# 03_MCU.net
KiCad netlist of a schematic drawn in Altium Designer
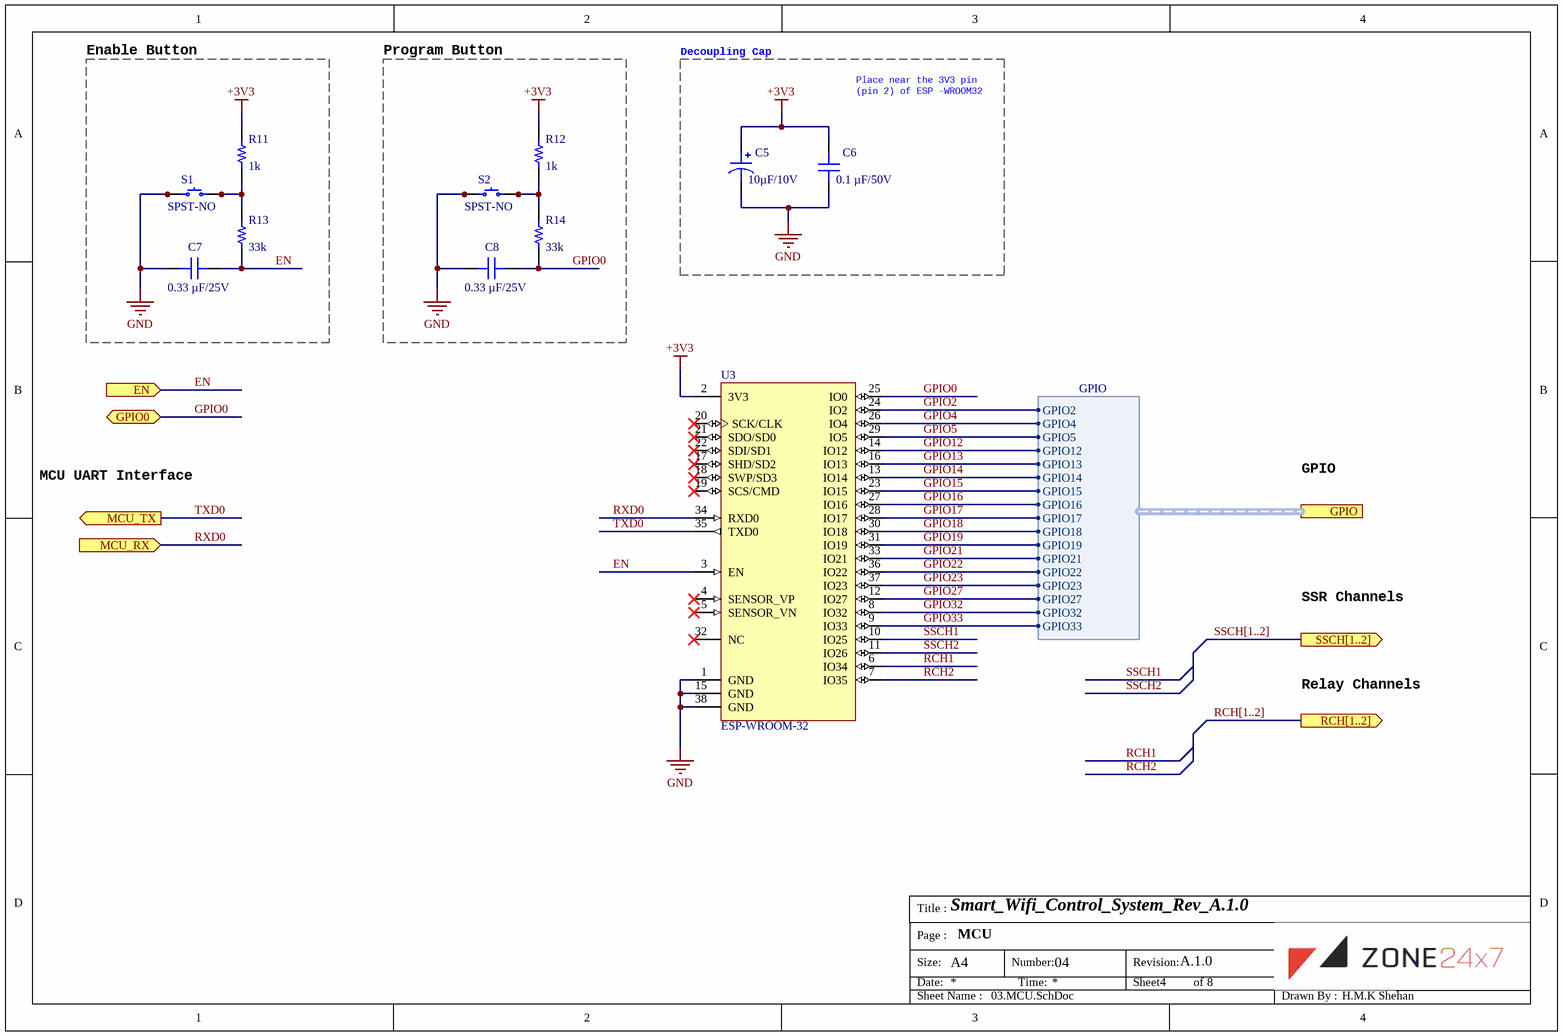
[diagram p0: 03.MCU.SchDoc]

(export (version "E")
  (design (tool "Eeschema 10.0.6"))
  (components
    (comp (ref "C5")
      (value "10µF/10V")
      (footprint "CAP POL 1411_3528")
      (description "10uF 10V 2.1Ω@100kHz ±10% 1411 Tantalum Capacitors ROHS")
      (fields
        (field (name "MANUFACTURER PART NUMBER") "TAJB106K010TNJ")
        (field (name "MANUFACTURER") "AVX Corporation")
      )
      (libsource (lib "Celestial Altium Library - altium_library") (part "Polarised Capacitor"))
    )
    (comp (ref "C6")
      (value "0.1 µF/50V")
      (footprint "CAP 0805_2012")
      (description "50V 100nF 2X1 ±10% 0805 Multilayer Ceramic Capacitors MLCC - SMD/SMT ROHS")
      (fields
        (field (name "MANUFACTURER PART NUMBER") "CT41G-0805-2X1-50V-0.1μF-K(N)")
        (field (name "MANUFACTURER") "TORCH")
      )
      (libsource (lib "Celestial Altium Library - altium_library") (part "Capacitor"))
    )
    (comp (ref "C7")
      (value "0.33 µF/25V")
      (footprint "CAP 0603_1608")
      (description "25V 330nF X7R ±10% 0603 Multilayer Ceramic Capacitors MLCC - SMD/SMT ROHS")
      (fields
        (field (name "MANUFACTURER PART NUMBER") "CC0603KRX7R8BB334")
        (field (name "MANUFACTURER") "Yageo")
      )
      (libsource (lib "Celestial Altium Library - altium_library") (part "Capacitor"))
    )
    (comp (ref "C8")
      (value "0.33 µF/25V")
      (footprint "CAP 0603_1608")
      (description "25V 330nF X7R ±10% 0603 Multilayer Ceramic Capacitors MLCC - SMD/SMT ROHS")
      (fields
        (field (name "MANUFACTURER PART NUMBER") "CC0603KRX7R8BB334")
        (field (name "MANUFACTURER") "Yageo")
      )
      (libsource (lib "Celestial Altium Library - altium_library") (part "Capacitor"))
    )
    (comp (ref "R11")
      (value "1k")
      (footprint "RES 0603_1608")
      (description "100mW ±100ppm/℃ ±1% 1kΩ 0603 Chip Resistor - Surface Mount ROHS")
      (fields (field (name "MANUFACTURER PART NUMBER") "RTT031001FTP") (field (name "MANUFACTURER") "RALEC"))
      (libsource (lib "Celestial Altium Library - altium_library") (part "Resistor"))
    )
    (comp (ref "R12")
      (value "1k")
      (footprint "RES 0603_1608")
      (description "100mW ±100ppm/℃ ±1% 1kΩ 0603 Chip Resistor - Surface Mount ROHS")
      (fields (field (name "MANUFACTURER PART NUMBER") "RTT031001FTP") (field (name "MANUFACTURER") "RALEC"))
      (libsource (lib "Celestial Altium Library - altium_library") (part "Resistor"))
    )
    (comp (ref "R13")
      (value "33k")
      (footprint "RES 0603_1608")
      (description "100mW ±100ppm/℃ ±1% 33kΩ 0603 Chip Resistor - Surface Mount ROHS")
      (fields (field (name "MANUFACTURER PART NUMBER") "RTT033302FTP") (field (name "MANUFACTURER") "RALEC"))
      (libsource (lib "Celestial Altium Library - altium_library") (part "Resistor"))
    )
    (comp (ref "R14")
      (value "33k")
      (footprint "RES 0603_1608")
      (description "100mW ±100ppm/℃ ±1% 33kΩ 0603 Chip Resistor - Surface Mount ROHS")
      (fields (field (name "MANUFACTURER PART NUMBER") "RTT033302FTP") (field (name "MANUFACTURER") "RALEC"))
      (libsource (lib "Celestial Altium Library - altium_library") (part "Resistor"))
    )
    (comp (ref "S1")
      (value "SPST-NO")
      (footprint "TE FSM4JSMA")
      (description "SWITCH TACTILE SPST-NO 0.05A 24V")
      (fields
        (field (name "MANUFACTURER PART NUMBER") "FSM4JSMATR")
        (field (name "MANUFACTURER") "TE Connectivity ALCOSWITCH Switches")
      )
      (libsource (lib "Celestial Altium Library - altium_library") (part "SPST-NO 4 PIN"))
    )
    (comp (ref "S2")
      (value "SPST-NO")
      (footprint "TE FSM4JSMA")
      (description "SWITCH TACTILE SPST-NO 0.05A 24V")
      (fields
        (field (name "MANUFACTURER PART NUMBER") "FSM4JSMATR")
        (field (name "MANUFACTURER") "TE Connectivity ALCOSWITCH Switches")
      )
      (libsource (lib "Celestial Altium Library - altium_library") (part "SPST-NO 4 PIN"))
    )
    (comp (ref "U3")
      (value "ESP-WROOM-32")
      (footprint "OLMX-ESP-WROOM-32")
      (description "SMD,18x25.5mm WiFi Modules ROHS")
      (fields
        (field (name "MANUFACTURER") "Espressif Systems")
        (field (name "MANUFACTURER PART NUMBER") "ESP32-WROOM-32-N4")
      )
      (libsource (lib "Smart_Wifi_Control_System_Rev_A.1.0") (part "OLMX-ESP-WROOM-32-38"))
    )
  )
  (nets
    (net (code "2") (name "+3V3") (class "Default")
      (node (ref "C5") (pin "1") (pinfunction "1_1") (pintype "passive"))
      (node (ref "C6") (pin "2") (pinfunction "2_2") (pintype "passive"))
      (node (ref "R11") (pin "2") (pinfunction "2_2") (pintype "passive"))
      (node (ref "R12") (pin "2") (pinfunction "2_2") (pintype "passive"))
      (node (ref "U3") (pin "2") (pinfunction "3V3_2") (pintype "power_in"))
    )
    (net (code "3") (name "/EN") (class "Default")
      (node (ref "C7") (pin "1") (pinfunction "1_1") (pintype "passive"))
      (node (ref "R13") (pin "1") (pinfunction "1_1") (pintype "passive"))
      (node (ref "U3") (pin "3") (pinfunction "EN_3") (pintype "input"))
    )
    (net (code "4") (name "/GPIO0") (class "Default")
      (node (ref "C8") (pin "1") (pinfunction "1_1") (pintype "passive"))
      (node (ref "R14") (pin "1") (pinfunction "1_1") (pintype "passive"))
      (node (ref "U3") (pin "25") (pinfunction "IO0_25") (pintype "bidirectional"))
    )
    (net (code "5") (name "/GPIO2") (class "Default")
      (node (ref "U3") (pin "24") (pinfunction "IO2_24") (pintype "bidirectional"))
    )
    (net (code "6") (name "/GPIO4") (class "Default")
      (node (ref "U3") (pin "26") (pinfunction "IO4_26") (pintype "bidirectional"))
    )
    (net (code "7") (name "/GPIO5") (class "Default")
      (node (ref "U3") (pin "29") (pinfunction "IO5_29") (pintype "bidirectional"))
    )
    (net (code "8") (name "/GPIO12") (class "Default")
      (node (ref "U3") (pin "14") (pinfunction "IO12_14") (pintype "bidirectional"))
    )
    (net (code "9") (name "/GPIO13") (class "Default")
      (node (ref "U3") (pin "16") (pinfunction "IO13_16") (pintype "bidirectional"))
    )
    (net (code "10") (name "/GPIO14") (class "Default")
      (node (ref "U3") (pin "13") (pinfunction "IO14_13") (pintype "bidirectional"))
    )
    (net (code "11") (name "/GPIO15") (class "Default")
      (node (ref "U3") (pin "23") (pinfunction "IO15_23") (pintype "bidirectional"))
    )
    (net (code "12") (name "/GPIO16") (class "Default")
      (node (ref "U3") (pin "27") (pinfunction "IO16_27") (pintype "bidirectional"))
    )
    (net (code "13") (name "/GPIO17") (class "Default")
      (node (ref "U3") (pin "28") (pinfunction "IO17_28") (pintype "bidirectional"))
    )
    (net (code "14") (name "/GPIO18") (class "Default")
      (node (ref "U3") (pin "30") (pinfunction "IO18_30") (pintype "bidirectional"))
    )
    (net (code "15") (name "/GPIO19") (class "Default")
      (node (ref "U3") (pin "31") (pinfunction "IO19_31") (pintype "bidirectional"))
    )
    (net (code "16") (name "/GPIO21") (class "Default")
      (node (ref "U3") (pin "33") (pinfunction "IO21_33") (pintype "bidirectional"))
    )
    (net (code "17") (name "/GPIO22") (class "Default")
      (node (ref "U3") (pin "36") (pinfunction "IO22_36") (pintype "bidirectional"))
    )
    (net (code "18") (name "/GPIO23") (class "Default")
      (node (ref "U3") (pin "37") (pinfunction "IO23_37") (pintype "bidirectional"))
    )
    (net (code "19") (name "/GPIO27") (class "Default")
      (node (ref "U3") (pin "12") (pinfunction "IO27_12") (pintype "bidirectional"))
    )
    (net (code "20") (name "/GPIO32") (class "Default")
      (node (ref "U3") (pin "8") (pinfunction "IO32_8") (pintype "bidirectional"))
    )
    (net (code "21") (name "/GPIO33") (class "Default")
      (node (ref "U3") (pin "9") (pinfunction "IO33_9") (pintype "bidirectional"))
    )
    (net (code "22") (name "/RCH1") (class "Default")
      (node (ref "U3") (pin "6") (pinfunction "IO34_6") (pintype "bidirectional"))
    )
    (net (code "23") (name "/RCH2") (class "Default")
      (node (ref "U3") (pin "7") (pinfunction "IO35_7") (pintype "bidirectional"))
    )
    (net (code "25") (name "/RXD0") (class "Default")
      (node (ref "U3") (pin "34") (pinfunction "RXD0_34") (pintype "input"))
    )
    (net (code "26") (name "/SSCH1") (class "Default")
      (node (ref "U3") (pin "10") (pinfunction "IO25_10") (pintype "bidirectional"))
    )
    (net (code "27") (name "/SSCH2") (class "Default")
      (node (ref "U3") (pin "11") (pinfunction "IO26_11") (pintype "bidirectional"))
    )
    (net (code "29") (name "/TXD0") (class "Default")
      (node (ref "U3") (pin "35") (pinfunction "TXD0_35") (pintype "output"))
    )
    (net (code "31") (name "GND") (class "Default")
      (node (ref "C5") (pin "2") (pinfunction "2_2") (pintype "passive"))
      (node (ref "C6") (pin "1") (pinfunction "1_1") (pintype "passive"))
      (node (ref "C7") (pin "2") (pinfunction "2_2") (pintype "passive"))
      (node (ref "C8") (pin "2") (pinfunction "2_2") (pintype "passive"))
      (node (ref "S1") (pin "1") (pinfunction "1_1") (pintype "passive"))
      (node (ref "S1") (pin "2") (pinfunction "2_2") (pintype "passive"))
      (node (ref "S2") (pin "1") (pinfunction "1_1") (pintype "passive"))
      (node (ref "S2") (pin "2") (pinfunction "2_2") (pintype "passive"))
      (node (ref "U3") (pin "1") (pinfunction "GND_1") (pintype "power_in"))
      (node (ref "U3") (pin "15") (pinfunction "GND_15") (pintype "power_in"))
      (node (ref "U3") (pin "38") (pinfunction "GND_38") (pintype "power_in"))
    )
    (net (code "32") (name "Net-(R11-Pad1)") (class "Default")
      (node (ref "R11") (pin "1") (pinfunction "1_1") (pintype "passive"))
      (node (ref "R13") (pin "2") (pinfunction "2_2") (pintype "passive"))
      (node (ref "S1") (pin "3") (pinfunction "3_3") (pintype "passive"))
      (node (ref "S1") (pin "4") (pinfunction "4_4") (pintype "passive"))
    )
    (net (code "33") (name "Net-(R12-Pad1)") (class "Default")
      (node (ref "R12") (pin "1") (pinfunction "1_1") (pintype "passive"))
      (node (ref "R14") (pin "2") (pinfunction "2_2") (pintype "passive"))
      (node (ref "S2") (pin "3") (pinfunction "3_3") (pintype "passive"))
      (node (ref "S2") (pin "4") (pinfunction "4_4") (pintype "passive"))
    )
    (net (code "34") (name "unconnected-(U3-NC-Pad32)") (class "Default")
      (node (ref "U3") (pin "32") (pinfunction "NC_32") (pintype "passive+no_connect"))
    )
    (net (code "35") (name "unconnected-(U3-SCK{slash}CLK-Pad20)") (class "Default")
      (node (ref "U3") (pin "20") (pinfunction "SCK/CLK_20") (pintype "bidirectional+no_connect"))
    )
    (net (code "36") (name "unconnected-(U3-SCS{slash}CMD-Pad19)") (class "Default")
      (node (ref "U3") (pin "19") (pinfunction "SCS/CMD_19") (pintype "bidirectional+no_connect"))
    )
    (net (code "37") (name "unconnected-(U3-SDI{slash}SD1-Pad22)") (class "Default")
      (node (ref "U3") (pin "22") (pinfunction "SDI/SD1_22") (pintype "bidirectional+no_connect"))
    )
    (net (code "38") (name "unconnected-(U3-SDO{slash}SD0-Pad21)") (class "Default")
      (node (ref "U3") (pin "21") (pinfunction "SDO/SD0_21") (pintype "bidirectional+no_connect"))
    )
    (net (code "39") (name "unconnected-(U3-SENSOR_VN-Pad5)") (class "Default")
      (node (ref "U3") (pin "5") (pinfunction "SENSOR_VN_5") (pintype "input+no_connect"))
    )
    (net (code "40") (name "unconnected-(U3-SENSOR_VP-Pad4)") (class "Default")
      (node (ref "U3") (pin "4") (pinfunction "SENSOR_VP_4") (pintype "input+no_connect"))
    )
    (net (code "41") (name "unconnected-(U3-SHD{slash}SD2-Pad17)") (class "Default")
      (node (ref "U3") (pin "17") (pinfunction "SHD/SD2_17") (pintype "bidirectional+no_connect"))
    )
    (net (code "42") (name "unconnected-(U3-SWP{slash}SD3-Pad18)") (class "Default")
      (node (ref "U3") (pin "18") (pinfunction "SWP/SD3_18") (pintype "bidirectional+no_connect"))
    )
  )
)
